# STM32.net
KiCad netlist of a schematic drawn in Altium Designer
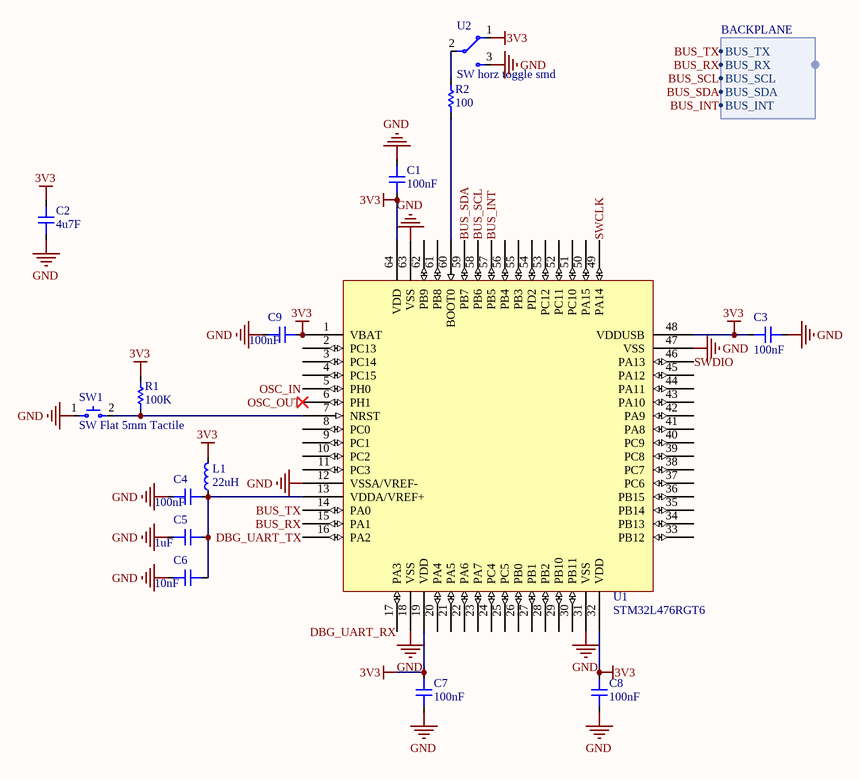
[diagram p0: STM32.SchDoc]

(export (version "E")
  (design (tool "Eeschema 10.0.6"))
  (components
    (comp (ref "C1")
      (value "100nF")
      (footprint "CAP 0805 L")
      (description "CAP 0805")
      (libsource (lib "streetbot") (part "CAP 0805"))
    )
    (comp (ref "C2")
      (value "4u7F")
      (footprint "CAP 0805 L")
      (description "CAP 0805")
      (libsource (lib "streetbot") (part "CAP 0805"))
    )
    (comp (ref "C3")
      (value "100nF")
      (footprint "CAP 0805 L")
      (description "CAP 0805")
      (libsource (lib "streetbot") (part "CAP 0805"))
    )
    (comp (ref "C4")
      (value "100nF")
      (footprint "CAP 0805 L")
      (description "CAP 0805")
      (libsource (lib "streetbot") (part "CAP 0805"))
    )
    (comp (ref "C5")
      (value "1uF")
      (footprint "CAP 0805 L")
      (description "CAP 0805")
      (libsource (lib "streetbot") (part "CAP 0805"))
    )
    (comp (ref "C6")
      (value "10nF")
      (footprint "CAP 0805 L")
      (description "CAP 0805")
      (libsource (lib "streetbot") (part "CAP 0805"))
    )
    (comp (ref "C7")
      (value "100nF")
      (footprint "CAP 0805 L")
      (description "CAP 0805")
      (libsource (lib "streetbot") (part "CAP 0805"))
    )
    (comp (ref "C8")
      (value "100nF")
      (footprint "CAP 0805 L")
      (description "CAP 0805")
      (libsource (lib "streetbot") (part "CAP 0805"))
    )
    (comp (ref "C9")
      (value "100nF")
      (footprint "CAP 0805 L")
      (description "CAP 0805")
      (libsource (lib "streetbot") (part "CAP 0805"))
    )
    (comp (ref "L1")
      (value "22uH")
      (footprint "IND 0805 L")
      (description "IND 0805")
      (libsource (lib "streetbot") (part "IND 0805"))
    )
    (comp (ref "R1")
      (value "100K")
      (footprint "RES 0603 L")
      (description "RES 0603")
      (libsource (lib "streetbot") (part "RES 0603"))
    )
    (comp (ref "R2")
      (value "100")
      (footprint "RES 0603 L")
      (description "RES 0603")
      (libsource (lib "streetbot") (part "RES 0603"))
    )
    (comp (ref "SW1")
      (value "SW Flat 5mm Tactile")
      (footprint "SW 5MM TACTILE")
      (libsource (lib "streetbot") (part "SW Flat 5mm Tactile"))
    )
    (comp (ref "U1")
      (value "STM32L476RGT6")
      (footprint "LQFP64")
      (libsource (lib "streetbot") (part "STM32L476RGT6"))
    )
    (comp (ref "U2") (value "SW horz toggle smd") (libsource (lib "streetbot") (part "SW horz toggle smd")))
  )
  (nets
    (net (code "1") (name "/BUS_INT") (class "Default")
      (node (ref "U1") (pin "57") (pinfunction "PB5_57") (pintype "bidirectional"))
    )
    (net (code "2") (name "/BUS_RX") (class "Default")
      (node (ref "U1") (pin "15") (pinfunction "PA1_15") (pintype "bidirectional"))
    )
    (net (code "3") (name "/BUS_SCL") (class "Default")
      (node (ref "U1") (pin "58") (pinfunction "PB6_58") (pintype "bidirectional"))
    )
    (net (code "4") (name "/BUS_SDA") (class "Default")
      (node (ref "U1") (pin "59") (pinfunction "PB7_59") (pintype "bidirectional"))
    )
    (net (code "5") (name "/BUS_TX") (class "Default")
      (node (ref "U1") (pin "14") (pinfunction "PA0_14") (pintype "bidirectional"))
    )
    (net (code "6") (name "/DBG_UART_RX") (class "Default")
      (node (ref "U1") (pin "17") (pinfunction "PA3_17") (pintype "bidirectional"))
    )
    (net (code "7") (name "/DBG_UART_TX") (class "Default")
      (node (ref "U1") (pin "16") (pinfunction "PA2_16") (pintype "bidirectional"))
    )
    (net (code "8") (name "/OSC_IN") (class "Default")
      (node (ref "U1") (pin "5") (pinfunction "PH0_5") (pintype "bidirectional"))
    )
    (net (code "9") (name "/OSC_OUT") (class "Default")
      (node (ref "U1") (pin "6") (pinfunction "PH1_6") (pintype "bidirectional+no_connect"))
    )
    (net (code "10") (name "/SWCLK") (class "Default")
      (node (ref "U1") (pin "49") (pinfunction "PA14_49") (pintype "bidirectional"))
    )
    (net (code "11") (name "/SWDIO") (class "Default")
      (node (ref "U1") (pin "46") (pinfunction "PA13_46") (pintype "bidirectional"))
    )
    (net (code "12") (name "3V3") (class "Default")
      (node (ref "C1") (pin "2") (pinfunction "2_2") (pintype "passive"))
      (node (ref "C2") (pin "1") (pinfunction "1_1") (pintype "passive"))
      (node (ref "C3") (pin "2") (pinfunction "2_2") (pintype "passive"))
      (node (ref "C7") (pin "2") (pinfunction "2_2") (pintype "passive"))
      (node (ref "C8") (pin "2") (pinfunction "2_2") (pintype "passive"))
      (node (ref "C9") (pin "2") (pinfunction "2_2") (pintype "passive"))
      (node (ref "L1") (pin "2") (pinfunction "2_2") (pintype "passive"))
      (node (ref "R1") (pin "2") (pinfunction "2_2") (pintype "passive"))
      (node (ref "U1") (pin "1") (pinfunction "VBAT_1") (pintype "power_in"))
      (node (ref "U1") (pin "19") (pinfunction "VDD_19") (pintype "power_in"))
      (node (ref "U1") (pin "32") (pinfunction "VDD_32") (pintype "power_in"))
      (node (ref "U1") (pin "48") (pinfunction "VDDUSB_48") (pintype "power_in"))
      (node (ref "U1") (pin "64") (pinfunction "VDD_64") (pintype "power_in"))
      (node (ref "U2") (pin "1") (pinfunction "1_1") (pintype "passive"))
    )
    (net (code "13") (name "GND") (class "Default")
      (node (ref "C1") (pin "1") (pinfunction "1_1") (pintype "passive"))
      (node (ref "C2") (pin "2") (pinfunction "2_2") (pintype "passive"))
      (node (ref "C3") (pin "1") (pinfunction "1_1") (pintype "passive"))
      (node (ref "C4") (pin "1") (pinfunction "1_1") (pintype "passive"))
      (node (ref "C5") (pin "1") (pinfunction "1_1") (pintype "passive"))
      (node (ref "C6") (pin "1") (pinfunction "1_1") (pintype "passive"))
      (node (ref "C7") (pin "1") (pinfunction "1_1") (pintype "passive"))
      (node (ref "C8") (pin "1") (pinfunction "1_1") (pintype "passive"))
      (node (ref "C9") (pin "1") (pinfunction "1_1") (pintype "passive"))
      (node (ref "SW1") (pin "1") (pinfunction "1_1") (pintype "passive"))
      (node (ref "U1") (pin "12") (pinfunction "VSSA/VREF-_12") (pintype "power_in"))
      (node (ref "U1") (pin "18") (pinfunction "VSS_18") (pintype "power_in"))
      (node (ref "U1") (pin "31") (pinfunction "VSS_31") (pintype "power_in"))
      (node (ref "U1") (pin "47") (pinfunction "VSS_47") (pintype "power_in"))
      (node (ref "U1") (pin "63") (pinfunction "VSS_63") (pintype "power_in"))
      (node (ref "U2") (pin "3") (pinfunction "3_3") (pintype "passive"))
    )
    (net (code "14") (name "Net-(R2-Pad2)") (class "Default")
      (node (ref "R2") (pin "2") (pinfunction "2_2") (pintype "passive"))
      (node (ref "U2") (pin "2") (pinfunction "2_2") (pintype "passive"))
    )
    (net (code "15") (name "Net-(U1-BOOT0)") (class "Default")
      (node (ref "R2") (pin "1") (pinfunction "1_1") (pintype "passive"))
      (node (ref "U1") (pin "60") (pinfunction "BOOT0_60") (pintype "input"))
    )
    (net (code "16") (name "Net-(U1-NRST)") (class "Default")
      (node (ref "R1") (pin "1") (pinfunction "1_1") (pintype "passive"))
      (node (ref "SW1") (pin "2") (pinfunction "2_2") (pintype "passive"))
      (node (ref "U1") (pin "7") (pinfunction "NRST_7") (pintype "input"))
    )
    (net (code "17") (name "Net-(U1-VDDA{slash}VREF+)") (class "Default")
      (node (ref "C4") (pin "2") (pinfunction "2_2") (pintype "passive"))
      (node (ref "C5") (pin "2") (pinfunction "2_2") (pintype "passive"))
      (node (ref "C6") (pin "2") (pinfunction "2_2") (pintype "passive"))
      (node (ref "L1") (pin "1") (pinfunction "1_1") (pintype "passive"))
      (node (ref "U1") (pin "13") (pinfunction "VDDA/VREF+_13") (pintype "power_in"))
    )
    (net (code "18") (name "unconnected-(U1-PA4-Pad20)") (class "Default")
      (node (ref "U1") (pin "20") (pinfunction "PA4_20") (pintype "bidirectional"))
    )
    (net (code "19") (name "unconnected-(U1-PA5-Pad21)") (class "Default")
      (node (ref "U1") (pin "21") (pinfunction "PA5_21") (pintype "bidirectional"))
    )
    (net (code "20") (name "unconnected-(U1-PA6-Pad22)") (class "Default")
      (node (ref "U1") (pin "22") (pinfunction "PA6_22") (pintype "bidirectional"))
    )
    (net (code "21") (name "unconnected-(U1-PA7-Pad23)") (class "Default")
      (node (ref "U1") (pin "23") (pinfunction "PA7_23") (pintype "bidirectional"))
    )
    (net (code "22") (name "unconnected-(U1-PA8-Pad41)") (class "Default")
      (node (ref "U1") (pin "41") (pinfunction "PA8_41") (pintype "bidirectional"))
    )
    (net (code "23") (name "unconnected-(U1-PA9-Pad42)") (class "Default")
      (node (ref "U1") (pin "42") (pinfunction "PA9_42") (pintype "bidirectional"))
    )
    (net (code "24") (name "unconnected-(U1-PA10-Pad43)") (class "Default")
      (node (ref "U1") (pin "43") (pinfunction "PA10_43") (pintype "bidirectional"))
    )
    (net (code "25") (name "unconnected-(U1-PA11-Pad44)") (class "Default")
      (node (ref "U1") (pin "44") (pinfunction "PA11_44") (pintype "bidirectional"))
    )
    (net (code "26") (name "unconnected-(U1-PA12-Pad45)") (class "Default")
      (node (ref "U1") (pin "45") (pinfunction "PA12_45") (pintype "bidirectional"))
    )
    (net (code "27") (name "unconnected-(U1-PA15-Pad50)") (class "Default")
      (node (ref "U1") (pin "50") (pinfunction "PA15_50") (pintype "bidirectional"))
    )
    (net (code "28") (name "unconnected-(U1-PB0-Pad26)") (class "Default")
      (node (ref "U1") (pin "26") (pinfunction "PB0_26") (pintype "bidirectional"))
    )
    (net (code "29") (name "unconnected-(U1-PB1-Pad27)") (class "Default")
      (node (ref "U1") (pin "27") (pinfunction "PB1_27") (pintype "bidirectional"))
    )
    (net (code "30") (name "unconnected-(U1-PB2-Pad28)") (class "Default")
      (node (ref "U1") (pin "28") (pinfunction "PB2_28") (pintype "bidirectional"))
    )
    (net (code "31") (name "unconnected-(U1-PB3-Pad55)") (class "Default")
      (node (ref "U1") (pin "55") (pinfunction "PB3_55") (pintype "bidirectional"))
    )
    (net (code "32") (name "unconnected-(U1-PB4-Pad56)") (class "Default")
      (node (ref "U1") (pin "56") (pinfunction "PB4_56") (pintype "bidirectional"))
    )
    (net (code "33") (name "unconnected-(U1-PB8-Pad61)") (class "Default")
      (node (ref "U1") (pin "61") (pinfunction "PB8_61") (pintype "bidirectional"))
    )
    (net (code "34") (name "unconnected-(U1-PB9-Pad62)") (class "Default")
      (node (ref "U1") (pin "62") (pinfunction "PB9_62") (pintype "bidirectional"))
    )
    (net (code "35") (name "unconnected-(U1-PB10-Pad29)") (class "Default")
      (node (ref "U1") (pin "29") (pinfunction "PB10_29") (pintype "bidirectional"))
    )
    (net (code "36") (name "unconnected-(U1-PB11-Pad30)") (class "Default")
      (node (ref "U1") (pin "30") (pinfunction "PB11_30") (pintype "bidirectional"))
    )
    (net (code "37") (name "unconnected-(U1-PB12-Pad33)") (class "Default")
      (node (ref "U1") (pin "33") (pinfunction "PB12_33") (pintype "bidirectional"))
    )
    (net (code "38") (name "unconnected-(U1-PB13-Pad34)") (class "Default")
      (node (ref "U1") (pin "34") (pinfunction "PB13_34") (pintype "bidirectional"))
    )
    (net (code "39") (name "unconnected-(U1-PB14-Pad35)") (class "Default")
      (node (ref "U1") (pin "35") (pinfunction "PB14_35") (pintype "bidirectional"))
    )
    (net (code "40") (name "unconnected-(U1-PB15-Pad36)") (class "Default")
      (node (ref "U1") (pin "36") (pinfunction "PB15_36") (pintype "bidirectional"))
    )
    (net (code "41") (name "unconnected-(U1-PC0-Pad8)") (class "Default")
      (node (ref "U1") (pin "8") (pinfunction "PC0_8") (pintype "bidirectional"))
    )
    (net (code "42") (name "unconnected-(U1-PC1-Pad9)") (class "Default")
      (node (ref "U1") (pin "9") (pinfunction "PC1_9") (pintype "bidirectional"))
    )
    (net (code "43") (name "unconnected-(U1-PC2-Pad10)") (class "Default")
      (node (ref "U1") (pin "10") (pinfunction "PC2_10") (pintype "bidirectional"))
    )
    (net (code "44") (name "unconnected-(U1-PC3-Pad11)") (class "Default")
      (node (ref "U1") (pin "11") (pinfunction "PC3_11") (pintype "bidirectional"))
    )
    (net (code "45") (name "unconnected-(U1-PC4-Pad24)") (class "Default")
      (node (ref "U1") (pin "24") (pinfunction "PC4_24") (pintype "bidirectional"))
    )
    (net (code "46") (name "unconnected-(U1-PC5-Pad25)") (class "Default")
      (node (ref "U1") (pin "25") (pinfunction "PC5_25") (pintype "bidirectional"))
    )
    (net (code "47") (name "unconnected-(U1-PC6-Pad37)") (class "Default")
      (node (ref "U1") (pin "37") (pinfunction "PC6_37") (pintype "bidirectional"))
    )
    (net (code "48") (name "unconnected-(U1-PC7-Pad38)") (class "Default")
      (node (ref "U1") (pin "38") (pinfunction "PC7_38") (pintype "bidirectional"))
    )
    (net (code "49") (name "unconnected-(U1-PC8-Pad39)") (class "Default")
      (node (ref "U1") (pin "39") (pinfunction "PC8_39") (pintype "bidirectional"))
    )
    (net (code "50") (name "unconnected-(U1-PC9-Pad40)") (class "Default")
      (node (ref "U1") (pin "40") (pinfunction "PC9_40") (pintype "bidirectional"))
    )
    (net (code "51") (name "unconnected-(U1-PC10-Pad51)") (class "Default")
      (node (ref "U1") (pin "51") (pinfunction "PC10_51") (pintype "bidirectional"))
    )
    (net (code "52") (name "unconnected-(U1-PC11-Pad52)") (class "Default")
      (node (ref "U1") (pin "52") (pinfunction "PC11_52") (pintype "bidirectional"))
    )
    (net (code "53") (name "unconnected-(U1-PC12-Pad53)") (class "Default")
      (node (ref "U1") (pin "53") (pinfunction "PC12_53") (pintype "bidirectional"))
    )
    (net (code "54") (name "unconnected-(U1-PC13-Pad2)") (class "Default")
      (node (ref "U1") (pin "2") (pinfunction "PC13_2") (pintype "bidirectional"))
    )
    (net (code "55") (name "unconnected-(U1-PC14-Pad3)") (class "Default")
      (node (ref "U1") (pin "3") (pinfunction "PC14_3") (pintype "bidirectional"))
    )
    (net (code "56") (name "unconnected-(U1-PC15-Pad4)") (class "Default")
      (node (ref "U1") (pin "4") (pinfunction "PC15_4") (pintype "bidirectional"))
    )
    (net (code "57") (name "unconnected-(U1-PD2-Pad54)") (class "Default")
      (node (ref "U1") (pin "54") (pinfunction "PD2_54") (pintype "bidirectional"))
    )
  )
)
